# sony_flash.net
KiCad netlist of a schematic drawn in EasyEDA Pro
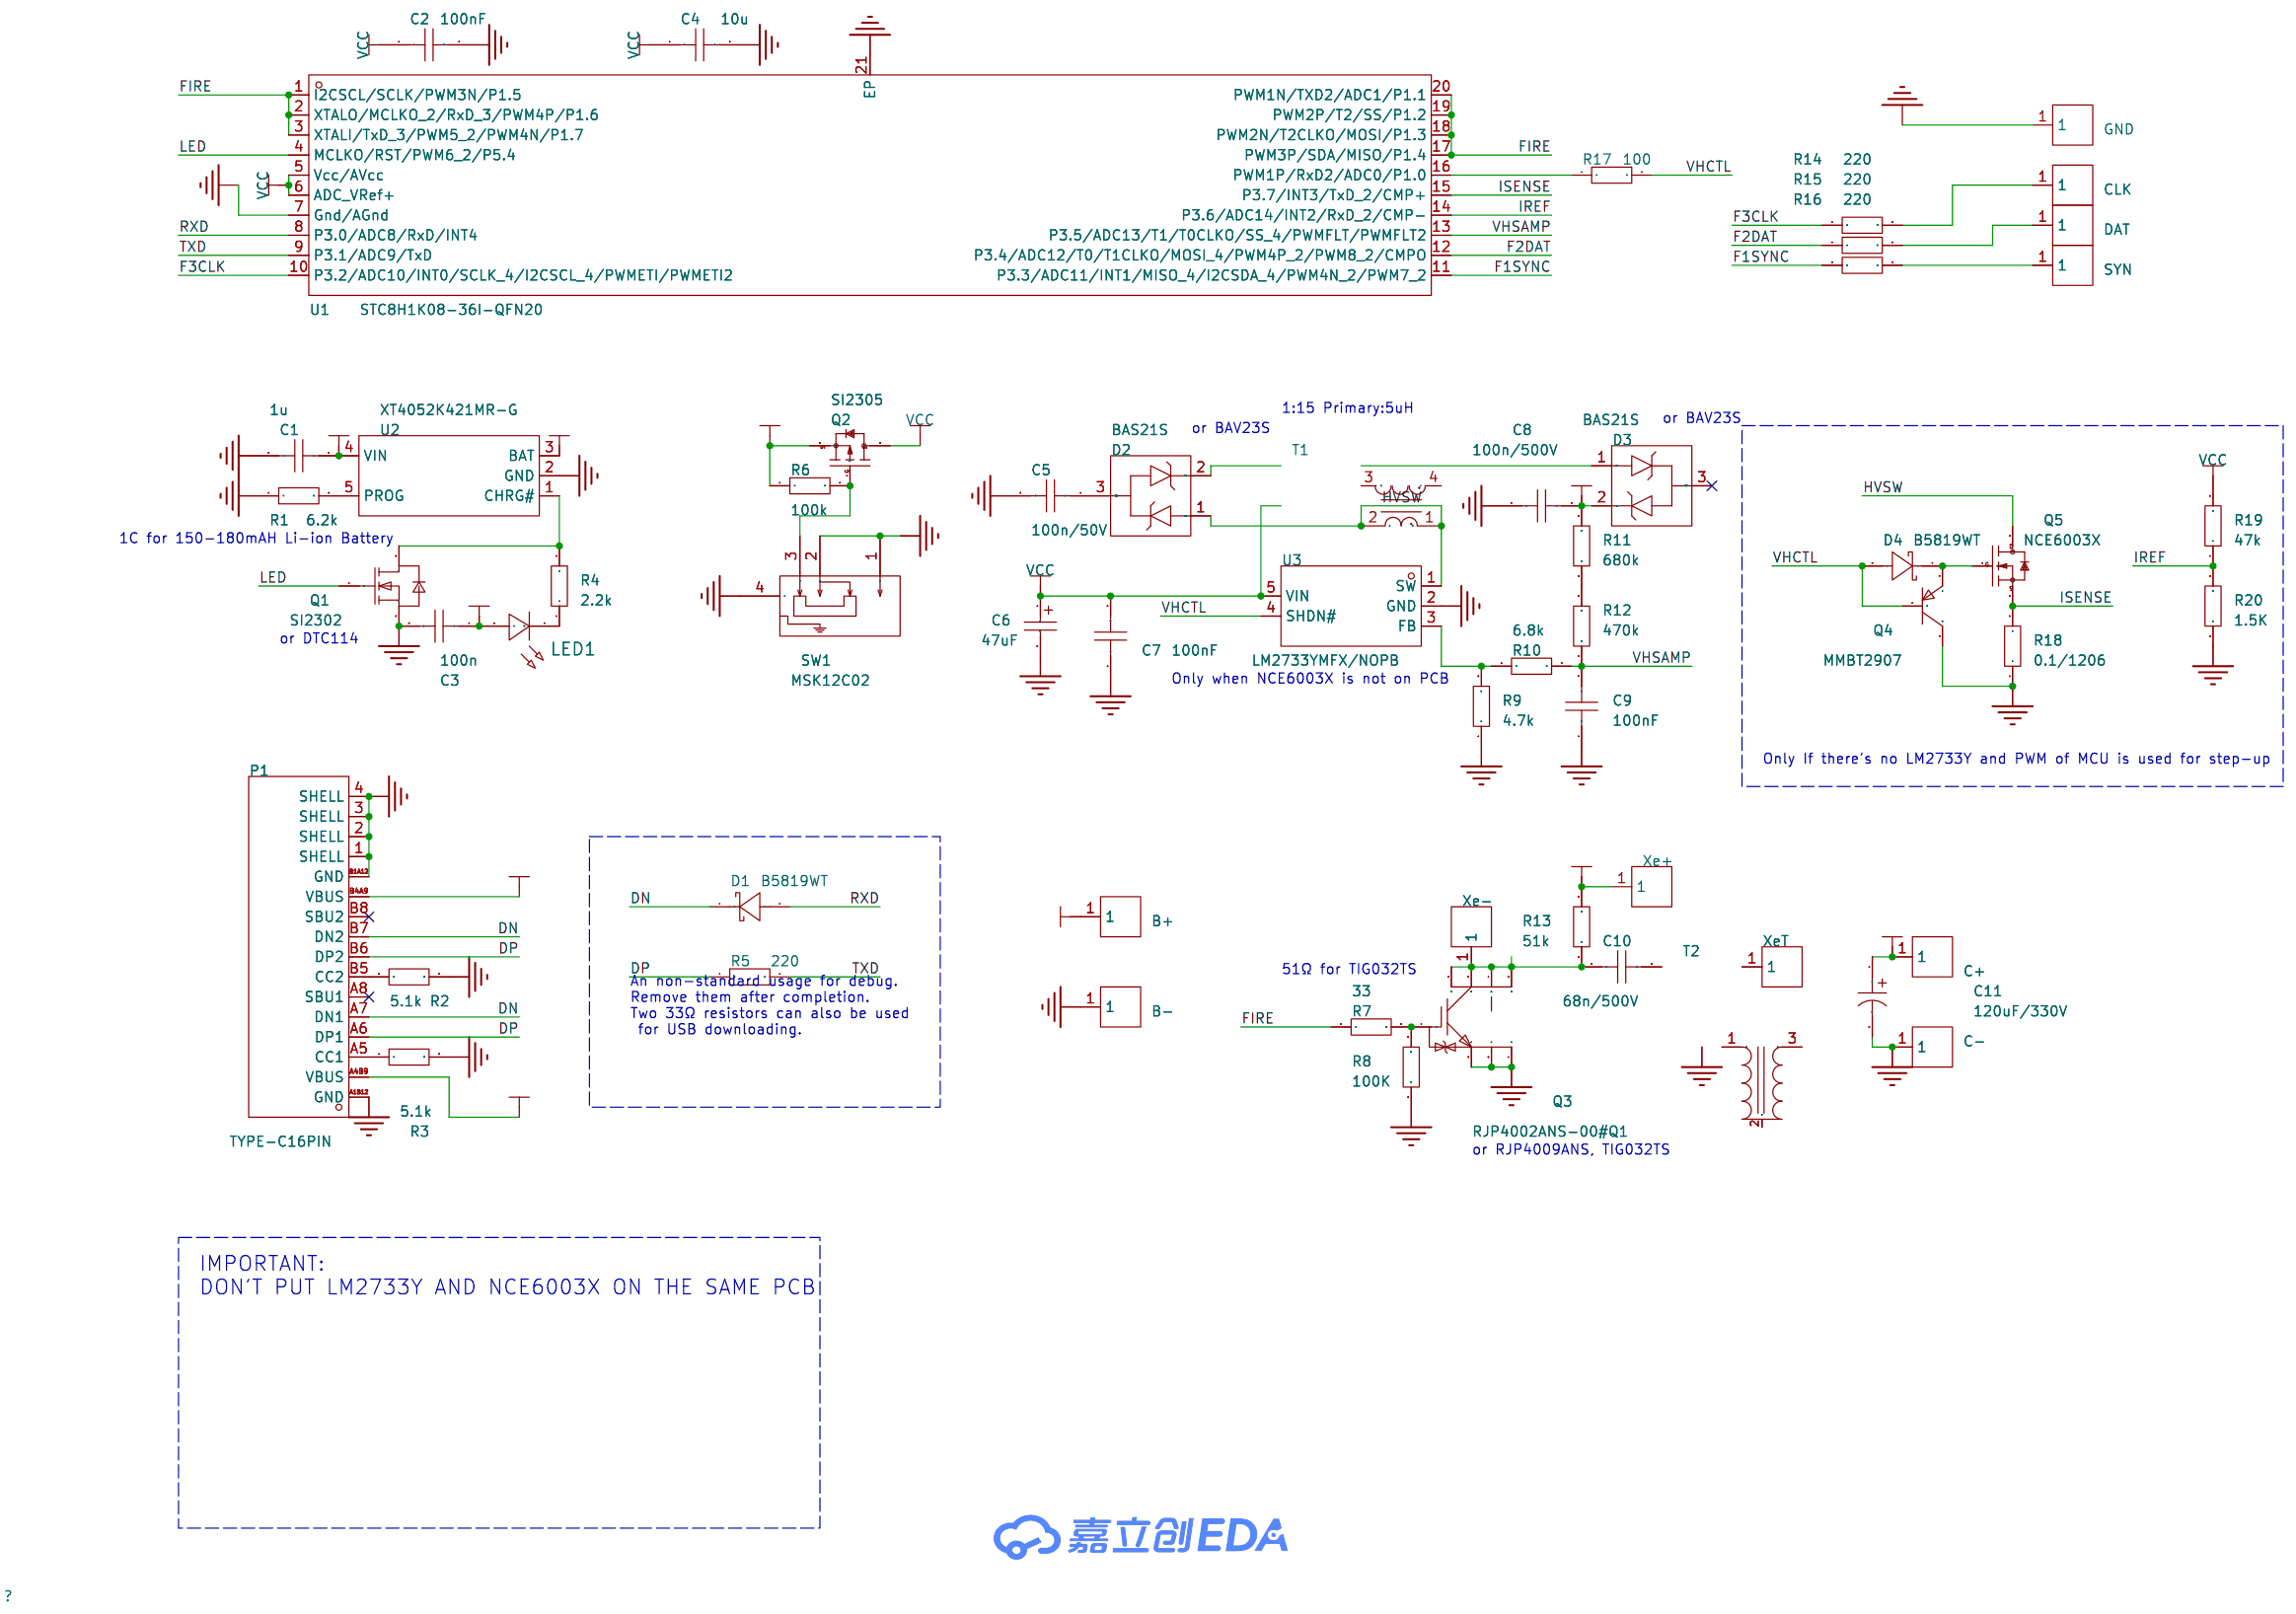
[diagram p0: schematic sheet]

(export (version "E")
  (design (tool "Eeschema 10.0.6"))
  (components
    (comp (ref "B+")
      (value "PAD")
      (footprint "easyedapro:SMD_BD4.0-L4.0-W4.0-D1.0")
      (libsource (lib "easyedapro") (part "PAD"))
    )
    (comp (ref "B-")
      (value "PAD")
      (footprint "easyedapro:SMD_BD4.0-L4.0-W4.0-D1.0")
      (libsource (lib "easyedapro") (part "PAD"))
    )
    (comp (ref "C+")
      (value "PAD")
      (footprint "easyedapro:SMD_BD4.0-L4.0-W4.0-D1.0")
      (libsource (lib "easyedapro") (part "PAD"))
    )
    (comp (ref "C-")
      (value "PAD")
      (footprint "easyedapro:SMD_BD4.0-L4.0-W4.0-D1.0")
      (libsource (lib "easyedapro") (part "PAD"))
    )
    (comp (ref "C1")
      (value "1u")
      (footprint "easyedapro:C0603")
      (libsource (lib "easyedapro") (part "Capacitance"))
    )
    (comp (ref "C2")
      (value "100nF")
      (footprint "easyedapro:C0603")
      (libsource (lib "easyedapro") (part "Capacitance"))
    )
    (comp (ref "C3")
      (value "100n")
      (footprint "easyedapro:C0603")
      (libsource (lib "easyedapro") (part "Capacitance"))
    )
    (comp (ref "C4")
      (value "10u")
      (footprint "easyedapro:C0603")
      (libsource (lib "easyedapro") (part "Capacitance"))
    )
    (comp (ref "C5")
      (value "100n/50V")
      (footprint "easyedapro:C0603")
      (libsource (lib "easyedapro") (part "Capacitance"))
    )
    (comp (ref "C6")
      (value "47uF")
      (footprint "easyedapro:CASE-A_3216")
      (description "容值:47uF;精度:±10%;额定电压:6.3V;等效串联电阻(ESR):1.6Ω@100kHz;")
      (fields (field (name "Manufacturer Part") "TAJA476K006RNJ") (field (name "Manufacturer") "Kyocera AVX"))
      (libsource (lib "easyedapro") (part "TAJA476K006RNJ"))
    )
    (comp (ref "C7")
      (value "100nF")
      (footprint "easyedapro:C0603")
      (libsource (lib "easyedapro") (part "Capacitance"))
    )
    (comp (ref "C8")
      (value "100n/500V")
      (footprint "easyedapro:C0603")
      (libsource (lib "easyedapro") (part "Capacitance"))
    )
    (comp (ref "C9")
      (value "100nF")
      (footprint "easyedapro:C0603")
      (libsource (lib "easyedapro") (part "Capacitance"))
    )
    (comp (ref "C10")
      (value "68n/500V")
      (footprint "easyedapro:C0603")
      (libsource (lib "easyedapro") (part "Capacitance"))
    )
    (comp (ref "C11")
      (value "120uF/330V")
      (footprint "easyedapro:CAP-TH_BD13.0-P5.00-D0.6-FD")
      (description "容值:120uF;精度:±20%;额定电压:400V;纹波电流:750mA@120Hz;等效串联电阻(ESR):-;")
      (fields (field (name "Manufacturer Part") "87EC0555") (field (name "Manufacturer") "KNSCHA(科尼盛)"))
      (libsource (lib "easyedapro") (part "87EC0555"))
    )
    (comp (ref "CLK")
      (value "PAD")
      (footprint "easyedapro:SMD_BD4.0-L4.0-W4.0-D1.0")
      (libsource (lib "easyedapro") (part "PAD"))
    )
    (comp (ref "D1")
      (value "B5819WT")
      (footprint "easyedapro:SOD-523_L1.2-W0.8-LS1.6-RD")
      (description "二极管配置:独立式;正向压降(Vf):600mV@200mA;直流反向耐压(Vr):40V;整流电流:350mA;")
      (fields (field (name "Manufacturer") "R+O(宏嘉诚)"))
      (libsource (lib "easyedapro") (part "B5819WT_C7502714"))
    )
    (comp (ref "D2")
      (value "BAS21S")
      (footprint "easyedapro:SOT-23_L2.9-W1.3-P1.90-LS2.4-BL")
      (description "二极管配置:1对串联式;正向压降(Vf):1.25V@200mA;直流反向耐压(Vr):250V;整流电流:200mA;反向恢复时间(Trr):50ns;")
      (fields (field (name "Manufacturer") "UMW(友台半导体)"))
      (libsource (lib "easyedapro") (part "BAS21S_C2846050"))
    )
    (comp (ref "D3")
      (value "BAS21S")
      (footprint "easyedapro:SOT-23_L2.9-W1.3-P1.90-LS2.4-BL")
      (description "二极管配置:1对串联式;正向压降(Vf):1.25V@200mA;直流反向耐压(Vr):250V;整流电流:200mA;反向恢复时间(Trr):50ns;")
      (fields (field (name "Manufacturer") "UMW(友台半导体)"))
      (libsource (lib "easyedapro") (part "BAS21S_C2846050"))
    )
    (comp (ref "D4")
      (value "B5819WT")
      (footprint "easyedapro:SOD-523_L1.2-W0.8-LS1.6-RD")
      (description "二极管配置:独立式;正向压降(Vf):600mV@200mA;直流反向耐压(Vr):40V;整流电流:350mA;")
      (fields (field (name "Manufacturer") "R+O(宏嘉诚)"))
      (libsource (lib "easyedapro") (part "B5819WT_C7502714"))
    )
    (comp (ref "DAT")
      (value "PAD")
      (footprint "easyedapro:SMD_BD4.0-L4.0-W4.0-D1.0")
      (libsource (lib "easyedapro") (part "PAD"))
    )
    (comp (ref "GND")
      (value "PAD")
      (footprint "easyedapro:SMD_BD4.0-L4.0-W4.0-D1.0")
      (libsource (lib "easyedapro") (part "PAD"))
    )
    (comp (ref "LED1")
      (value "~")
      (footprint "easyedapro:LED_0603")
      (libsource (lib "easyedapro") (part "LED_R"))
    )
    (comp (ref "P1")
      (value "TYPE-C16PIN")
      (footprint "easyedapro:USB-C-SMD_TYPE-C16PIN")
      (description "连接器类型:Type-C;协议标准:USB 3.1;公母:母;安装方式:卧贴;触点数量:16P;端口数量:1;额定电流 - 电源:3A;工作温度:-40°C~+85°C;")
      (fields (field (name "Manufacturer") "SHOU HAN(首韩)"))
      (libsource (lib "easyedapro") (part "TYPE-C16PIN"))
    )
    (comp (ref "Q1")
      (value "SI2302")
      (footprint "easyedapro:SOT-23-3_L2.9-W1.3-P0.95-LS2.4-BR")
      (libsource (lib "easyedapro") (part "SI2302_C9900175661"))
    )
    (comp (ref "Q2")
      (value "SI2305")
      (footprint "easyedapro:SOT-23-3_L2.9-W1.3-P1.90-LS2.4-BR")
      (fields (field (name "Manufacturer") "Hottech(合科泰)"))
      (libsource (lib "easyedapro") (part "SI2305"))
    )
    (comp (ref "Q3")
      (value "RJP4002ANS-00#Q1")
      (footprint "easyedapro:VSON-8_L4.4-W3.0-P0.65-LS4.8-BL")
      (fields (field (name "Manufacturer") "RENESAS(瑞萨)/IDT"))
      (libsource (lib "easyedapro") (part "RJP4002ANS-00#Q1"))
    )
    (comp (ref "Q4")
      (value "MMBT2907")
      (footprint "easyedapro:SOT-23-3_L2.9-W1.3-P1.90-LS2.4-BR")
      (description "晶体管类型:PNP;集电极电流(Ic):600mA;集射极击穿电压(Vceo):60V;耗散功率(Pd):225mW;直流电流增益(hFE):400@150mA,10V;")
      (fields (field (name "Manufacturer") "YONGYUTAI(永裕泰)"))
      (libsource (lib "easyedapro") (part "MMBT2907_C2891811"))
    )
    (comp (ref "Q5")
      (value "NCE6003X")
      (footprint "easyedapro:SOT-23-3_L2.9-W1.3-P1.90-LS2.4-BR")
      (fields (field (name "Manufacturer") "NCE(无锡新洁能)"))
      (libsource (lib "easyedapro") (part "NCE6003X"))
    )
    (comp (ref "R1") (value "6.2k") (footprint "easyedapro:R0603") (libsource (lib "easyedapro") (part "电阻")))
    (comp (ref "R2") (value "5.1k") (footprint "easyedapro:R0603") (libsource (lib "easyedapro") (part "电阻")))
    (comp (ref "R3") (value "5.1k") (footprint "easyedapro:R0603") (libsource (lib "easyedapro") (part "电阻")))
    (comp (ref "R4") (value "2.2k") (footprint "easyedapro:R0603") (libsource (lib "easyedapro") (part "电阻")))
    (comp (ref "R5") (value "220") (footprint "easyedapro:R0603") (libsource (lib "easyedapro") (part "电阻")))
    (comp (ref "R6") (value "100k") (footprint "easyedapro:R0603") (libsource (lib "easyedapro") (part "电阻")))
    (comp (ref "R7") (value "33") (footprint "easyedapro:R0603") (libsource (lib "easyedapro") (part "电阻")))
    (comp (ref "R8") (value "100K") (footprint "easyedapro:R0603") (libsource (lib "easyedapro") (part "电阻")))
    (comp (ref "R9") (value "4.7k") (footprint "easyedapro:R0603") (libsource (lib "easyedapro") (part "电阻")))
    (comp (ref "R10")
      (value "6.8k")
      (footprint "easyedapro:R0603")
      (libsource (lib "easyedapro") (part "电阻"))
    )
    (comp (ref "R11")
      (value "680k")
      (footprint "easyedapro:R0603")
      (libsource (lib "easyedapro") (part "电阻"))
    )
    (comp (ref "R12")
      (value "470k")
      (footprint "easyedapro:R0603")
      (libsource (lib "easyedapro") (part "电阻"))
    )
    (comp (ref "R13") (value "51k") (footprint "easyedapro:R0603") (libsource (lib "easyedapro") (part "电阻")))
    (comp (ref "R14") (value "220") (footprint "easyedapro:R0603") (libsource (lib "easyedapro") (part "电阻")))
    (comp (ref "R15") (value "220") (footprint "easyedapro:R0603") (libsource (lib "easyedapro") (part "电阻")))
    (comp (ref "R16") (value "220") (footprint "easyedapro:R0603") (libsource (lib "easyedapro") (part "电阻")))
    (comp (ref "R17") (value "100") (footprint "easyedapro:R0603") (libsource (lib "easyedapro") (part "电阻")))
    (comp (ref "R18")
      (value "0.1/1206")
      (footprint "easyedapro:R0603")
      (libsource (lib "easyedapro") (part "电阻"))
    )
    (comp (ref "R19") (value "47k") (footprint "easyedapro:R0603") (libsource (lib "easyedapro") (part "电阻")))
    (comp (ref "R20")
      (value "1.5K")
      (footprint "easyedapro:R0603")
      (libsource (lib "easyedapro") (part "电阻"))
    )
    (comp (ref "SW1")
      (value "MSK12C02")
      (footprint "easyedapro:SW-TH_MSK12C02")
      (description "电路结构:单刀双掷;安装方式:卧贴;开关颜色:-;额定电流:50mA;额定电压:12V;工作寿命:1万次;")
      (fields (field (name "Manufacturer") "SHOU HAN(首韩)"))
      (libsource (lib "easyedapro") (part "MSK12C02"))
    )
    (comp (ref "SYN")
      (value "PAD")
      (footprint "easyedapro:SMD_BD4.0-L4.0-W4.0-D1.0")
      (libsource (lib "easyedapro") (part "PAD"))
    )
    (comp (ref "T1")
      (value "~")
      (footprint "easyedapro:NA5924-AR")
      (libsource (lib "easyedapro") (part "transformer-2-2"))
    )
    (comp (ref "T2")
      (value "~")
      (footprint "easyedapro:TTRG-HF8124")
      (libsource (lib "easyedapro") (part "transform-3p"))
    )
    (comp (ref "U1")
      (value "STC8H1K08-36I-QFN20")
      (footprint "easyedapro:QFN-20_L3.0-W3.0-P0.40-BL-EP1.7")
      (description "CPU内核:51系列;应用领域:-;")
      (fields (field (name "Manufacturer") "STC"))
      (libsource (lib "easyedapro") (part "STC8H1K08-36I-QFN20"))
    )
    (comp (ref "U2")
      (value "XT4052K421MR-G")
      (footprint "easyedapro:SOT-23-5_L2.9-W1.6-P0.95-LS2.8-BL")
      (fields (field (name "Manufacturer") "natlinear(南麟)"))
      (libsource (lib "easyedapro") (part "XT4052K421MR-G"))
    )
    (comp (ref "U3")
      (value "LM2733YMFX/NOPB")
      (footprint "easyedapro:SOT-23-5_L3.0-W1.7-P0.95-LS2.8-BL")
      (description "功能类型:升压型;工作电压:2.7V~14V;输出电压:2.7V~40V;输出电流:1A;输出类型:可调;")
      (fields (field (name "Manufacturer") "TI(德州仪器)"))
      (libsource (lib "easyedapro") (part "LM2733YMFX/NOPB"))
    )
    (comp (ref "Xe+")
      (value "PAD")
      (footprint "easyedapro:SMD_BD4.0-L4.0-W4.0-D1.0")
      (libsource (lib "easyedapro") (part "PAD"))
    )
    (comp (ref "Xe-")
      (value "PAD")
      (footprint "easyedapro:SMD_BD4.0-L4.0-W4.0-D1.0")
      (libsource (lib "easyedapro") (part "PAD"))
    )
    (comp (ref "XeT")
      (value "PAD")
      (footprint "easyedapro:SMD_BD4.0-L4.0-W4.0-D1.0")
      (libsource (lib "easyedapro") (part "PAD"))
    )
  )
  (nets
    (net (code "1") (name "/DN") (class "Default")
      (node (ref "D1") (pin "1") (pinfunction "K_1") (pintype "unspecified"))
      (node (ref "P1") (pin "A7") (pinfunction "DN1_A7") (pintype "unspecified"))
      (node (ref "P1") (pin "B7") (pinfunction "DN2_B7") (pintype "unspecified"))
    )
    (net (code "2") (name "/DP") (class "Default")
      (node (ref "P1") (pin "A6") (pinfunction "DP1_A6") (pintype "unspecified"))
      (node (ref "P1") (pin "B6") (pinfunction "DP2_B6") (pintype "unspecified"))
      (node (ref "R5") (pin "1") (pinfunction "1_1") (pintype "input"))
    )
    (net (code "3") (name "/F1SYNC") (class "Default")
      (node (ref "R16") (pin "1") (pinfunction "1_1") (pintype "input"))
      (node (ref "U1") (pin "11") (pinfunction "P3.3/ADC11/INT1/MISO_4/I2CSDA_4/PWM4N_2/PWM7_2_11") (pintype "unspecified"))
    )
    (net (code "4") (name "/F2DAT") (class "Default")
      (node (ref "R15") (pin "1") (pinfunction "1_1") (pintype "input"))
      (node (ref "U1") (pin "12") (pinfunction "P3.4/ADC12/T0/T1CLKO/MOSI_4/PWM4P_2/PWM8_2/CMPO_12") (pintype "unspecified"))
    )
    (net (code "5") (name "/F3CLK") (class "Default")
      (node (ref "R14") (pin "1") (pinfunction "1_1") (pintype "input"))
      (node (ref "U1") (pin "10") (pinfunction "P3.2/ADC10/INT0/SCLK_4/I2CSCL_4/PWMETI/PWMETI2_10") (pintype "unspecified"))
    )
    (net (code "6") (name "/FIRE") (class "Default")
      (node (ref "R7") (pin "1") (pinfunction "1_1") (pintype "input"))
      (node (ref "U1") (pin "1") (pinfunction "I2CSCL/SCLK/PWM3N/P1.5_1") (pintype "unspecified"))
      (node (ref "U1") (pin "17") (pinfunction "PWM3P/SDA/MISO/P1.4_17") (pintype "unspecified"))
      (node (ref "U1") (pin "18") (pinfunction "PWM2N/T2CLKO/MOSI/P1.3_18") (pintype "unspecified"))
      (node (ref "U1") (pin "19") (pinfunction "PWM2P/T2/SS/P1.2_19") (pintype "unspecified"))
      (node (ref "U1") (pin "2") (pinfunction "XTALO/MCLKO_2/RxD_3/PWM4P/P1.6_2") (pintype "unspecified"))
      (node (ref "U1") (pin "20") (pinfunction "PWM1N/TXD2/ADC1/P1.1_20") (pintype "unspecified"))
      (node (ref "U1") (pin "3") (pinfunction "XTALI/TxD_3/PWM5_2/PWM4N/P1.7_3") (pintype "unspecified"))
    )
    (net (code "7") (name "/HVSW") (class "Default")
      (node (ref "D2") (pin "1") (pinfunction "BASE_1") (pintype "unspecified"))
      (node (ref "Q5") (pin "3") (pinfunction "D_3") (pintype "unspecified"))
      (node (ref "T1") (pin "1") (pinfunction "1_1") (pintype "input"))
      (node (ref "T1") (pin "2") (pinfunction "2_2") (pintype "input"))
      (node (ref "U3") (pin "1") (pinfunction "SW_1") (pintype "unspecified"))
    )
    (net (code "8") (name "/IREF") (class "Default")
      (node (ref "R19") (pin "1") (pinfunction "1_1") (pintype "input"))
      (node (ref "R20") (pin "2") (pinfunction "2_2") (pintype "input"))
      (node (ref "U1") (pin "14") (pinfunction "P3.6/ADC14/INT2/RxD_2/CMP-_14") (pintype "unspecified"))
    )
    (net (code "9") (name "/ISENSE") (class "Default")
      (node (ref "Q5") (pin "2") (pinfunction "S_2") (pintype "unspecified"))
      (node (ref "R18") (pin "2") (pinfunction "2_2") (pintype "input"))
      (node (ref "U1") (pin "15") (pinfunction "P3.7/INT3/TxD_2/CMP+_15") (pintype "unspecified"))
    )
    (net (code "10") (name "/LED") (class "Default")
      (node (ref "Q1") (pin "1") (pinfunction "G_1") (pintype "unspecified"))
      (node (ref "U1") (pin "4") (pinfunction "MCLKO/RST/PWM6_2/P5.4_4") (pintype "unspecified"))
    )
    (net (code "11") (name "/RXD") (class "Default")
      (node (ref "D1") (pin "2") (pinfunction "A_2") (pintype "unspecified"))
      (node (ref "U1") (pin "8") (pinfunction "P3.0/ADC8/RxD/INT4_8") (pintype "unspecified"))
    )
    (net (code "12") (name "/TXD") (class "Default")
      (node (ref "R5") (pin "2") (pinfunction "2_2") (pintype "input"))
      (node (ref "U1") (pin "9") (pinfunction "P3.1/ADC9/TxD_9") (pintype "unspecified"))
    )
    (net (code "13") (name "/VHCTL") (class "Default")
      (node (ref "D4") (pin "2") (pinfunction "A_2") (pintype "unspecified"))
      (node (ref "Q4") (pin "1") (pinfunction "B_1") (pintype "input"))
      (node (ref "R17") (pin "2") (pinfunction "2_2") (pintype "input"))
      (node (ref "U3") (pin "4") (pinfunction "SHDN#_4") (pintype "unspecified"))
    )
    (net (code "14") (name "/VHSAMP") (class "Default")
      (node (ref "C9") (pin "2") (pinfunction "2_2") (pintype "input"))
      (node (ref "R10") (pin "2") (pinfunction "2_2") (pintype "input"))
      (node (ref "R12") (pin "1") (pinfunction "1_1") (pintype "input"))
      (node (ref "U1") (pin "13") (pinfunction "P3.5/ADC13/T1/T0CLKO/SS_4/PWMFLT/PWMFLT2_13") (pintype "unspecified"))
    )
    (net (code "15") (name "GND") (class "Default")
      (node (ref "B-") (pin "1") (pinfunction "1_1") (pintype "unspecified"))
      (node (ref "C-") (pin "1") (pinfunction "1_1") (pintype "unspecified"))
      (node (ref "C1") (pin "2") (pinfunction "2_2") (pintype "input"))
      (node (ref "C11") (pin "2") (pinfunction "2_2") (pintype "input"))
      (node (ref "C2") (pin "2") (pinfunction "2_2") (pintype "input"))
      (node (ref "C3") (pin "2") (pinfunction "2_2") (pintype "input"))
      (node (ref "C4") (pin "2") (pinfunction "2_2") (pintype "input"))
      (node (ref "C5") (pin "2") (pinfunction "2_2") (pintype "input"))
      (node (ref "C6") (pin "2") (pinfunction "2_2") (pintype "input"))
      (node (ref "C7") (pin "1") (pinfunction "1_1") (pintype "input"))
      (node (ref "C8") (pin "1") (pinfunction "1_1") (pintype "input"))
      (node (ref "C9") (pin "1") (pinfunction "1_1") (pintype "input"))
      (node (ref "GND") (pin "1") (pinfunction "1_1") (pintype "unspecified"))
      (node (ref "P1") (pin "1") (pinfunction "SHELL_1") (pintype "unspecified"))
      (node (ref "P1") (pin "2") (pinfunction "SHELL_2") (pintype "unspecified"))
      (node (ref "P1") (pin "3") (pinfunction "SHELL_3") (pintype "unspecified"))
      (node (ref "P1") (pin "4") (pinfunction "SHELL_4") (pintype "unspecified"))
      (node (ref "P1") (pin "A1B12") (pinfunction "GND_A1B12") (pintype "unspecified"))
      (node (ref "P1") (pin "B1A12") (pinfunction "GND_B1A12") (pintype "unspecified"))
      (node (ref "Q1") (pin "2") (pinfunction "S_2") (pintype "unspecified"))
      (node (ref "Q3") (pin "1") (pinfunction "E_1") (pintype "input"))
      (node (ref "Q3") (pin "2") (pinfunction "E_2") (pintype "input"))
      (node (ref "Q3") (pin "3") (pinfunction "E_3") (pintype "input"))
      (node (ref "Q4") (pin "3") (pinfunction "C_3") (pintype "input"))
      (node (ref "R1") (pin "1") (pinfunction "1_1") (pintype "input"))
      (node (ref "R18") (pin "1") (pinfunction "1_1") (pintype "input"))
      (node (ref "R2") (pin "2") (pinfunction "2_2") (pintype "input"))
      (node (ref "R20") (pin "1") (pinfunction "1_1") (pintype "input"))
      (node (ref "R3") (pin "2") (pinfunction "2_2") (pintype "input"))
      (node (ref "R8") (pin "1") (pinfunction "1_1") (pintype "input"))
      (node (ref "R9") (pin "1") (pinfunction "1_1") (pintype "input"))
      (node (ref "SW1") (pin "1") (pinfunction "1_1") (pintype "unspecified"))
      (node (ref "SW1") (pin "2") (pinfunction "2_2") (pintype "unspecified"))
      (node (ref "SW1") (pin "4") (pinfunction "4_4") (pintype "unspecified"))
      (node (ref "U1") (pin "21") (pinfunction "EP_21") (pintype "unspecified"))
      (node (ref "U1") (pin "7") (pinfunction "Gnd/AGnd_7") (pintype "unspecified"))
      (node (ref "U2") (pin "2") (pinfunction "GND_2") (pintype "unspecified"))
      (node (ref "U3") (pin "2") (pinfunction "GND_2") (pintype "unspecified"))
    )
    (net (code "16") (name "Net-(C10-Pad1)") (class "Default")
      (node (ref "C10") (pin "1") (pinfunction "1_1") (pintype "input"))
      (node (ref "Q3") (pin "5") (pinfunction "C_5") (pintype "input"))
      (node (ref "Q3") (pin "6") (pinfunction "C_6") (pintype "input"))
      (node (ref "Q3") (pin "7") (pinfunction "C_7") (pintype "input"))
      (node (ref "Q3") (pin "8") (pinfunction "C_8") (pintype "input"))
      (node (ref "R13") (pin "1") (pinfunction "1_1") (pintype "input"))
      (node (ref "Xe-") (pin "1") (pinfunction "1_1") (pintype "unspecified"))
    )
    (net (code "17") (name "Net-(CLK-Pad1)") (class "Default")
      (node (ref "CLK") (pin "1") (pinfunction "1_1") (pintype "unspecified"))
      (node (ref "R14") (pin "2") (pinfunction "2_2") (pintype "input"))
    )
    (net (code "18") (name "Net-(D2-COLLECTOR)") (class "Default")
      (node (ref "C5") (pin "1") (pinfunction "1_1") (pintype "input"))
      (node (ref "D2") (pin "3") (pinfunction "COLLECTOR_3") (pintype "unspecified"))
    )
    (net (code "19") (name "Net-(D4-K)") (class "Default")
      (node (ref "D4") (pin "1") (pinfunction "K_1") (pintype "unspecified"))
      (node (ref "Q4") (pin "2") (pinfunction "E_2") (pintype "input"))
      (node (ref "Q5") (pin "1") (pinfunction "G_1") (pintype "unspecified"))
    )
    (net (code "20") (name "Net-(DAT-Pad1)") (class "Default")
      (node (ref "DAT") (pin "1") (pinfunction "1_1") (pintype "unspecified"))
      (node (ref "R15") (pin "2") (pinfunction "2_2") (pintype "input"))
    )
    (net (code "21") (name "Net-(LED1-C)") (class "Default")
      (node (ref "LED1") (pin "1") (pinfunction "C_1") (pintype "input"))
      (node (ref "R4") (pin "1") (pinfunction "1_1") (pintype "input"))
    )
    (net (code "22") (name "Net-(P1-CC1)") (class "Default")
      (node (ref "P1") (pin "A5") (pinfunction "CC1_A5") (pintype "unspecified"))
      (node (ref "R3") (pin "1") (pinfunction "1_1") (pintype "input"))
    )
    (net (code "23") (name "Net-(P1-CC2)") (class "Default")
      (node (ref "P1") (pin "B5") (pinfunction "CC2_B5") (pintype "unspecified"))
      (node (ref "R2") (pin "1") (pinfunction "1_1") (pintype "input"))
    )
    (net (code "24") (name "Net-(Q1-D)") (class "Default")
      (node (ref "Q1") (pin "3") (pinfunction "D_3") (pintype "unspecified"))
      (node (ref "R4") (pin "2") (pinfunction "2_2") (pintype "input"))
      (node (ref "U2") (pin "1") (pinfunction "CHRG#_1") (pintype "unspecified"))
    )
    (net (code "25") (name "Net-(Q2-G)") (class "Default")
      (node (ref "Q2") (pin "1") (pinfunction "G_1") (pintype "unspecified"))
      (node (ref "R6") (pin "2") (pinfunction "2_2") (pintype "input"))
      (node (ref "SW1") (pin "3") (pinfunction "3_3") (pintype "unspecified"))
    )
    (net (code "26") (name "Net-(Q3-G)") (class "Default")
      (node (ref "Q3") (pin "4") (pinfunction "G_4") (pintype "input"))
      (node (ref "R7") (pin "2") (pinfunction "2_2") (pintype "input"))
      (node (ref "R8") (pin "2") (pinfunction "2_2") (pintype "input"))
    )
    (net (code "27") (name "Net-(R11-Pad1)") (class "Default")
      (node (ref "R11") (pin "1") (pinfunction "1_1") (pintype "input"))
      (node (ref "R12") (pin "2") (pinfunction "2_2") (pintype "input"))
    )
    (net (code "28") (name "Net-(R16-Pad2)") (class "Default")
      (node (ref "R16") (pin "2") (pinfunction "2_2") (pintype "input"))
      (node (ref "SYN") (pin "1") (pinfunction "1_1") (pintype "unspecified"))
    )
    (net (code "29") (name "Net-(U1-PWM1P{slash}RxD2{slash}ADC0{slash}P1.0)") (class "Default")
      (node (ref "R17") (pin "1") (pinfunction "1_1") (pintype "input"))
      (node (ref "U1") (pin "16") (pinfunction "PWM1P/RxD2/ADC0/P1.0_16") (pintype "unspecified"))
    )
    (net (code "30") (name "Net-(U2-PROG)") (class "Default")
      (node (ref "R1") (pin "2") (pinfunction "2_2") (pintype "input"))
      (node (ref "U2") (pin "5") (pinfunction "PROG_5") (pintype "unspecified"))
    )
    (net (code "31") (name "Net-(U3-FB)") (class "Default")
      (node (ref "R10") (pin "1") (pinfunction "1_1") (pintype "input"))
      (node (ref "R9") (pin "2") (pinfunction "2_2") (pintype "input"))
      (node (ref "U3") (pin "3") (pinfunction "FB_3") (pintype "unspecified"))
    )
    (net (code "32") (name "VBAT") (class "Default")
      (node (ref "B+") (pin "1") (pinfunction "1_1") (pintype "unspecified"))
      (node (ref "C3") (pin "1") (pinfunction "1_1") (pintype "input"))
      (node (ref "LED1") (pin "2") (pinfunction "A_2") (pintype "input"))
      (node (ref "Q2") (pin "2") (pinfunction "S_2") (pintype "unspecified"))
      (node (ref "R6") (pin "1") (pinfunction "1_1") (pintype "input"))
      (node (ref "U2") (pin "3") (pinfunction "BAT_3") (pintype "unspecified"))
    )
    (net (code "33") (name "VBUS") (class "Default")
      (node (ref "C1") (pin "1") (pinfunction "1_1") (pintype "input"))
      (node (ref "P1") (pin "A4B9") (pinfunction "VBUS_A4B9") (pintype "unspecified"))
      (node (ref "P1") (pin "B4A9") (pinfunction "VBUS_B4A9") (pintype "unspecified"))
      (node (ref "U2") (pin "4") (pinfunction "VIN_4") (pintype "unspecified"))
    )
    (net (code "34") (name "VCC") (class "Default")
      (node (ref "C2") (pin "1") (pinfunction "1_1") (pintype "input"))
      (node (ref "C4") (pin "1") (pinfunction "1_1") (pintype "input"))
      (node (ref "C6") (pin "1") (pinfunction "1_1") (pintype "input"))
      (node (ref "C7") (pin "2") (pinfunction "2_2") (pintype "input"))
      (node (ref "Q2") (pin "3") (pinfunction "D_3") (pintype "unspecified"))
      (node (ref "R19") (pin "2") (pinfunction "2_2") (pintype "input"))
      (node (ref "U1") (pin "5") (pinfunction "Vcc/AVcc_5") (pintype "unspecified"))
      (node (ref "U1") (pin "6") (pinfunction "ADC_VRef+_6") (pintype "unspecified"))
      (node (ref "U3") (pin "5") (pinfunction "VIN_5") (pintype "unspecified"))
    )
    (net (code "35") (name "VH") (class "Default")
      (node (ref "C+") (pin "1") (pinfunction "1_1") (pintype "unspecified"))
      (node (ref "C11") (pin "1") (pinfunction "1_1") (pintype "input"))
      (node (ref "C8") (pin "2") (pinfunction "2_2") (pintype "input"))
      (node (ref "D3") (pin "2") (pinfunction "EMITTER_2") (pintype "unspecified"))
      (node (ref "R11") (pin "2") (pinfunction "2_2") (pintype "input"))
      (node (ref "R13") (pin "2") (pinfunction "2_2") (pintype "input"))
      (node (ref "Xe+") (pin "1") (pinfunction "1_1") (pintype "unspecified"))
    )
    (net (code "36") (name "unconnected-(C10-Pad2)") (class "Default")
      (node (ref "C10") (pin "2") (pinfunction "2_2") (pintype "input"))
    )
    (net (code "37") (name "unconnected-(D2-EMITTER-Pad2)") (class "Default")
      (node (ref "D2") (pin "2") (pinfunction "EMITTER_2") (pintype "unspecified"))
    )
    (net (code "38") (name "unconnected-(D3-BASE-Pad1)") (class "Default")
      (node (ref "D3") (pin "1") (pinfunction "BASE_1") (pintype "unspecified"))
    )
    (net (code "39") (name "unconnected-(D3-COLLECTOR-Pad3)") (class "Default")
      (node (ref "D3") (pin "3") (pinfunction "COLLECTOR_3") (pintype "unspecified+no_connect"))
    )
    (net (code "40") (name "unconnected-(P1-SBU1-PadA8)") (class "Default")
      (node (ref "P1") (pin "A8") (pinfunction "SBU1_A8") (pintype "unspecified+no_connect"))
    )
    (net (code "41") (name "unconnected-(P1-SBU2-PadB8)") (class "Default")
      (node (ref "P1") (pin "B8") (pinfunction "SBU2_B8") (pintype "unspecified+no_connect"))
    )
    (net (code "42") (name "unconnected-(T1-Pad3)") (class "Default")
      (node (ref "T1") (pin "3") (pinfunction "3_3") (pintype "input"))
    )
    (net (code "43") (name "unconnected-(T1-Pad4)") (class "Default")
      (node (ref "T1") (pin "4") (pinfunction "4_4") (pintype "input"))
    )
    (net (code "44") (name "unconnected-(T2-Pad1)") (class "Default")
      (node (ref "T2") (pin "1") (pinfunction "1_1") (pintype "input"))
    )
    (net (code "45") (name "unconnected-(T2-Pad2)") (class "Default")
      (node (ref "T2") (pin "2") (pinfunction "2_2") (pintype "input"))
    )
    (net (code "46") (name "unconnected-(T2-Pad3)") (class "Default")
      (node (ref "T2") (pin "3") (pinfunction "3_3") (pintype "input"))
    )
    (net (code "47") (name "unconnected-(XeT-Pad1)") (class "Default")
      (node (ref "XeT") (pin "1") (pinfunction "1_1") (pintype "unspecified"))
    )
  )
)
